# Power_toll.net
KiCad netlist of a schematic drawn in Altium Designer
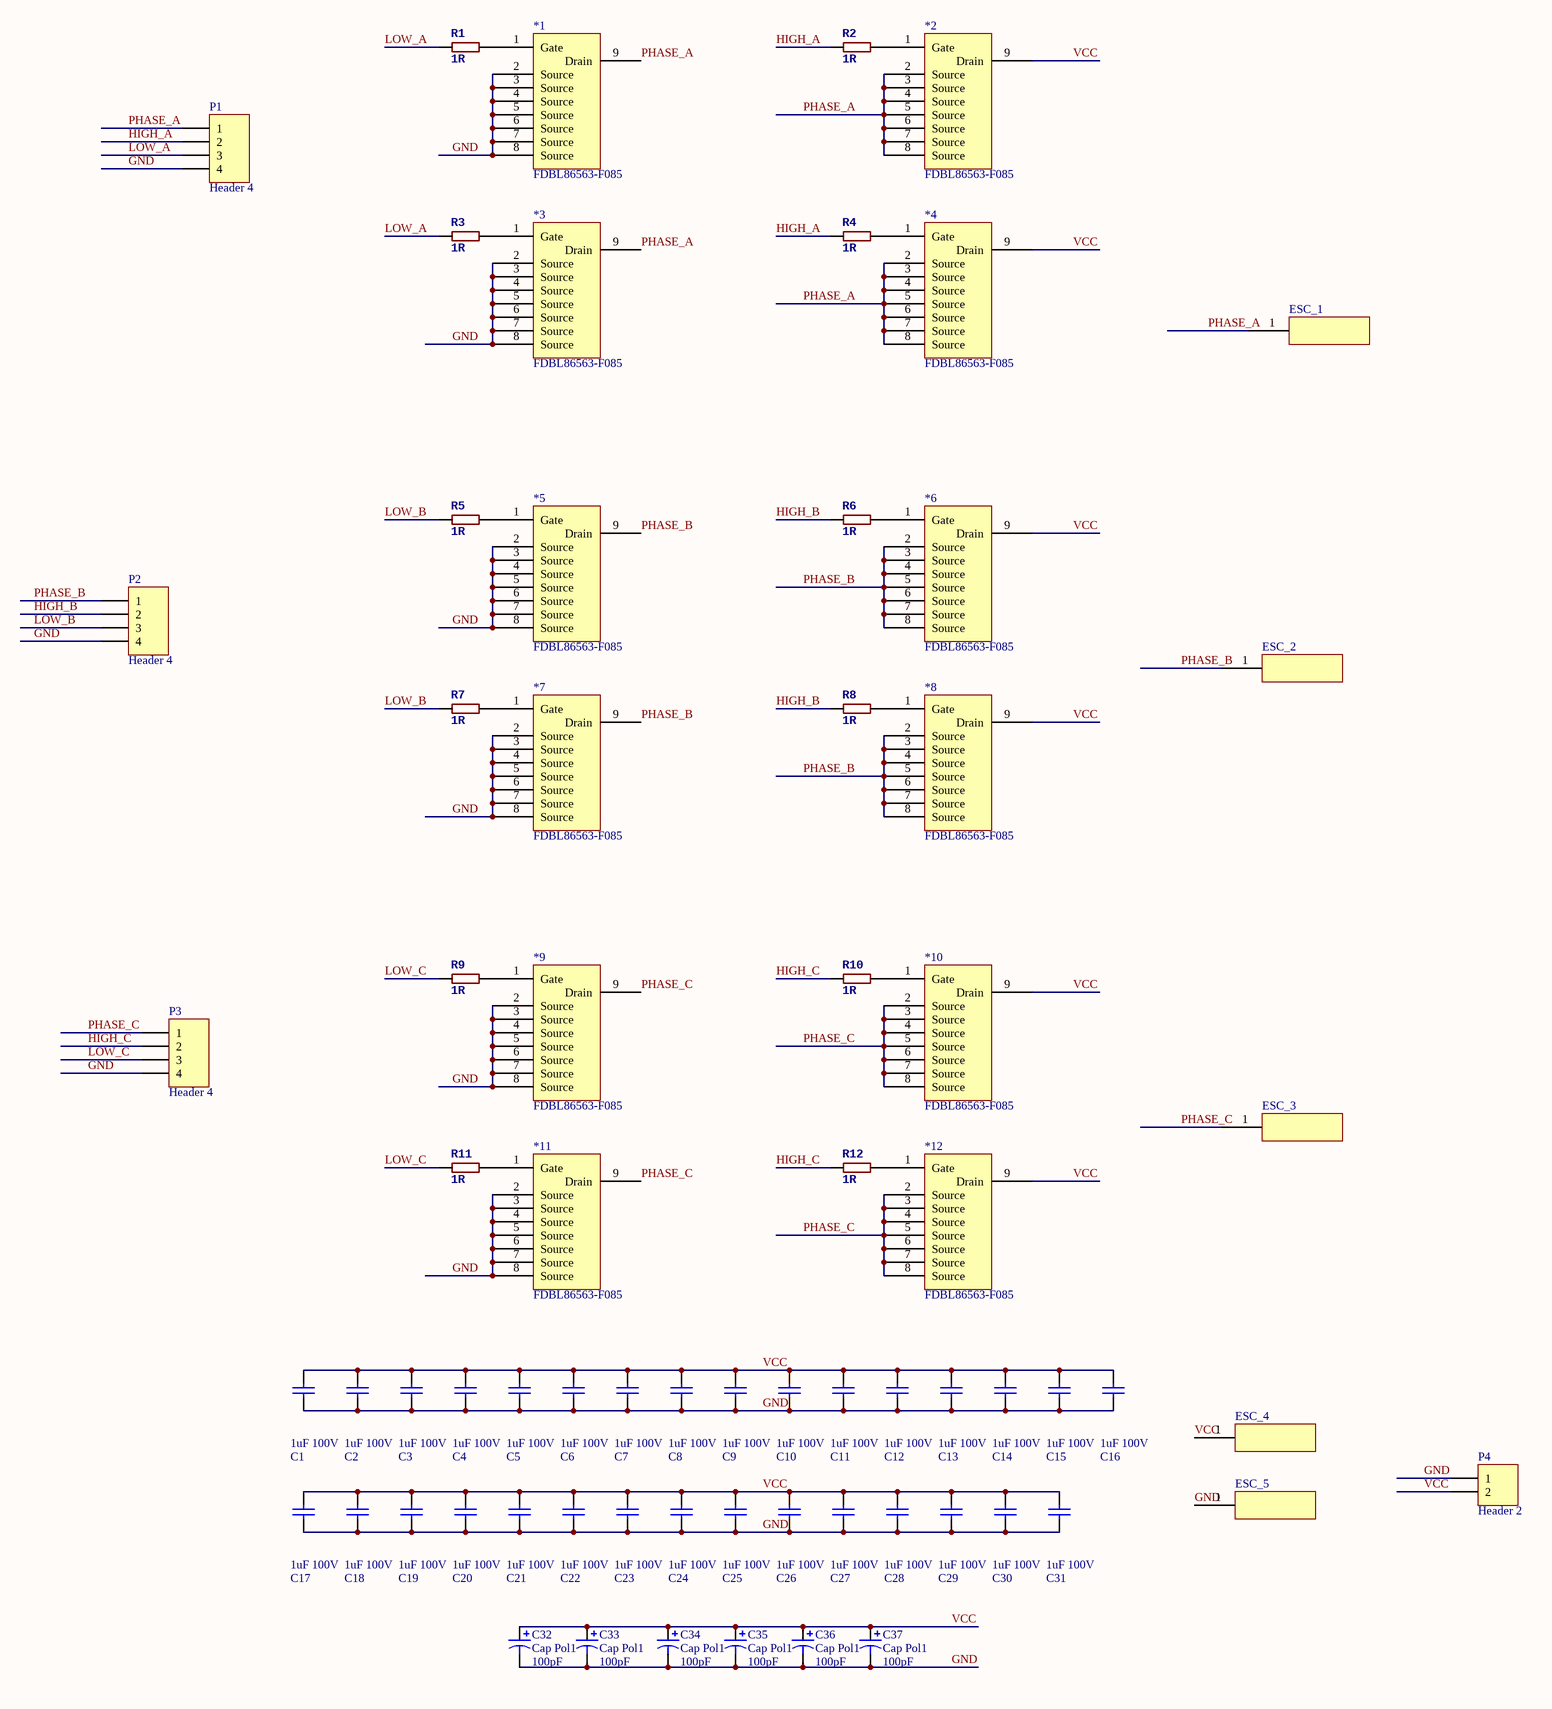
[diagram p0: Power_toll.SchDoc]

(export (version "E")
  (design (tool "Eeschema 10.0.6"))
  (components
    (comp (ref "*1")
      (value "FDBL86563-F085")
      (footprint "FDBL86563-F085")
      (libsource (lib "FDBL86563-F085") (part "FDBL86563-F085"))
    )
    (comp (ref "*2")
      (value "FDBL86563-F085")
      (footprint "FDBL86563-F085")
      (libsource (lib "FDBL86563-F085") (part "FDBL86563-F085"))
    )
    (comp (ref "*3")
      (value "FDBL86563-F085")
      (footprint "FDBL86563-F085")
      (libsource (lib "FDBL86563-F085") (part "FDBL86563-F085"))
    )
    (comp (ref "*4")
      (value "FDBL86563-F085")
      (footprint "FDBL86563-F085")
      (libsource (lib "FDBL86563-F085") (part "FDBL86563-F085"))
    )
    (comp (ref "*5")
      (value "FDBL86563-F085")
      (footprint "FDBL86563-F085")
      (libsource (lib "FDBL86563-F085") (part "FDBL86563-F085"))
    )
    (comp (ref "*6")
      (value "FDBL86563-F085")
      (footprint "FDBL86563-F085")
      (libsource (lib "FDBL86563-F085") (part "FDBL86563-F085"))
    )
    (comp (ref "*7")
      (value "FDBL86563-F085")
      (footprint "FDBL86563-F085")
      (libsource (lib "FDBL86563-F085") (part "FDBL86563-F085"))
    )
    (comp (ref "*8")
      (value "FDBL86563-F085")
      (footprint "FDBL86563-F085")
      (libsource (lib "FDBL86563-F085") (part "FDBL86563-F085"))
    )
    (comp (ref "*9")
      (value "FDBL86563-F085")
      (footprint "FDBL86563-F085")
      (libsource (lib "FDBL86563-F085") (part "FDBL86563-F085"))
    )
    (comp (ref "*10")
      (value "FDBL86563-F085")
      (footprint "FDBL86563-F085")
      (libsource (lib "FDBL86563-F085") (part "FDBL86563-F085"))
    )
    (comp (ref "*11")
      (value "FDBL86563-F085")
      (footprint "FDBL86563-F085")
      (libsource (lib "FDBL86563-F085") (part "FDBL86563-F085"))
    )
    (comp (ref "*12")
      (value "FDBL86563-F085")
      (footprint "FDBL86563-F085")
      (libsource (lib "FDBL86563-F085") (part "FDBL86563-F085"))
    )
    (comp (ref "C1")
      (value "1uF 100V")
      (footprint "C1206")
      (description "Capacitor (Semiconductor SIM Model)")
      (fields (field (name "PUBLISHER") "Altium Limited"))
      (libsource (lib "Miscellaneous Devices") (part "Cap Semi"))
    )
    (comp (ref "C2")
      (value "1uF 100V")
      (footprint "C1206")
      (description "Capacitor (Semiconductor SIM Model)")
      (fields (field (name "PUBLISHER") "Altium Limited"))
      (libsource (lib "Miscellaneous Devices") (part "Cap Semi"))
    )
    (comp (ref "C3")
      (value "1uF 100V")
      (footprint "C1206")
      (description "Capacitor (Semiconductor SIM Model)")
      (fields (field (name "PUBLISHER") "Altium Limited"))
      (libsource (lib "Miscellaneous Devices") (part "Cap Semi"))
    )
    (comp (ref "C4")
      (value "1uF 100V")
      (footprint "C1206")
      (description "Capacitor (Semiconductor SIM Model)")
      (fields (field (name "PUBLISHER") "Altium Limited"))
      (libsource (lib "Miscellaneous Devices") (part "Cap Semi"))
    )
    (comp (ref "C5")
      (value "1uF 100V")
      (footprint "C1206")
      (description "Capacitor (Semiconductor SIM Model)")
      (fields (field (name "PUBLISHER") "Altium Limited"))
      (libsource (lib "Miscellaneous Devices") (part "Cap Semi"))
    )
    (comp (ref "C6")
      (value "1uF 100V")
      (footprint "C1206")
      (description "Capacitor (Semiconductor SIM Model)")
      (fields (field (name "PUBLISHER") "Altium Limited"))
      (libsource (lib "Miscellaneous Devices") (part "Cap Semi"))
    )
    (comp (ref "C7")
      (value "1uF 100V")
      (footprint "C1206")
      (description "Capacitor (Semiconductor SIM Model)")
      (fields (field (name "PUBLISHER") "Altium Limited"))
      (libsource (lib "Miscellaneous Devices") (part "Cap Semi"))
    )
    (comp (ref "C8")
      (value "1uF 100V")
      (footprint "C1206")
      (description "Capacitor (Semiconductor SIM Model)")
      (fields (field (name "PUBLISHER") "Altium Limited"))
      (libsource (lib "Miscellaneous Devices") (part "Cap Semi"))
    )
    (comp (ref "C9")
      (value "1uF 100V")
      (footprint "C1206")
      (description "Capacitor (Semiconductor SIM Model)")
      (fields (field (name "PUBLISHER") "Altium Limited"))
      (libsource (lib "Miscellaneous Devices") (part "Cap Semi"))
    )
    (comp (ref "C10")
      (value "1uF 100V")
      (footprint "C1206")
      (description "Capacitor (Semiconductor SIM Model)")
      (fields (field (name "PUBLISHER") "Altium Limited"))
      (libsource (lib "Miscellaneous Devices") (part "Cap Semi"))
    )
    (comp (ref "C11")
      (value "1uF 100V")
      (footprint "C1206")
      (description "Capacitor (Semiconductor SIM Model)")
      (fields (field (name "PUBLISHER") "Altium Limited"))
      (libsource (lib "Miscellaneous Devices") (part "Cap Semi"))
    )
    (comp (ref "C12")
      (value "1uF 100V")
      (footprint "C1206")
      (description "Capacitor (Semiconductor SIM Model)")
      (fields (field (name "PUBLISHER") "Altium Limited"))
      (libsource (lib "Miscellaneous Devices") (part "Cap Semi"))
    )
    (comp (ref "C13")
      (value "1uF 100V")
      (footprint "C1206")
      (description "Capacitor (Semiconductor SIM Model)")
      (fields (field (name "PUBLISHER") "Altium Limited"))
      (libsource (lib "Miscellaneous Devices") (part "Cap Semi"))
    )
    (comp (ref "C14")
      (value "1uF 100V")
      (footprint "C1206")
      (description "Capacitor (Semiconductor SIM Model)")
      (fields (field (name "PUBLISHER") "Altium Limited"))
      (libsource (lib "Miscellaneous Devices") (part "Cap Semi"))
    )
    (comp (ref "C15")
      (value "1uF 100V")
      (footprint "C1206")
      (description "Capacitor (Semiconductor SIM Model)")
      (fields (field (name "PUBLISHER") "Altium Limited"))
      (libsource (lib "Miscellaneous Devices") (part "Cap Semi"))
    )
    (comp (ref "C16")
      (value "1uF 100V")
      (footprint "C1206")
      (description "Capacitor (Semiconductor SIM Model)")
      (fields (field (name "PUBLISHER") "Altium Limited"))
      (libsource (lib "Miscellaneous Devices") (part "Cap Semi"))
    )
    (comp (ref "C17")
      (value "1uF 100V")
      (footprint "C1206")
      (description "Capacitor (Semiconductor SIM Model)")
      (fields (field (name "PUBLISHER") "Altium Limited"))
      (libsource (lib "Miscellaneous Devices") (part "Cap Semi"))
    )
    (comp (ref "C18")
      (value "1uF 100V")
      (footprint "C1206")
      (description "Capacitor (Semiconductor SIM Model)")
      (fields (field (name "PUBLISHER") "Altium Limited"))
      (libsource (lib "Miscellaneous Devices") (part "Cap Semi"))
    )
    (comp (ref "C19")
      (value "1uF 100V")
      (footprint "C1206")
      (description "Capacitor (Semiconductor SIM Model)")
      (fields (field (name "PUBLISHER") "Altium Limited"))
      (libsource (lib "Miscellaneous Devices") (part "Cap Semi"))
    )
    (comp (ref "C20")
      (value "1uF 100V")
      (footprint "C1206")
      (description "Capacitor (Semiconductor SIM Model)")
      (fields (field (name "PUBLISHER") "Altium Limited"))
      (libsource (lib "Miscellaneous Devices") (part "Cap Semi"))
    )
    (comp (ref "C21")
      (value "1uF 100V")
      (footprint "C1206")
      (description "Capacitor (Semiconductor SIM Model)")
      (fields (field (name "PUBLISHER") "Altium Limited"))
      (libsource (lib "Miscellaneous Devices") (part "Cap Semi"))
    )
    (comp (ref "C22")
      (value "1uF 100V")
      (footprint "C1206")
      (description "Capacitor (Semiconductor SIM Model)")
      (fields (field (name "PUBLISHER") "Altium Limited"))
      (libsource (lib "Miscellaneous Devices") (part "Cap Semi"))
    )
    (comp (ref "C23")
      (value "1uF 100V")
      (footprint "C1206")
      (description "Capacitor (Semiconductor SIM Model)")
      (fields (field (name "PUBLISHER") "Altium Limited"))
      (libsource (lib "Miscellaneous Devices") (part "Cap Semi"))
    )
    (comp (ref "C24")
      (value "1uF 100V")
      (footprint "C1206")
      (description "Capacitor (Semiconductor SIM Model)")
      (fields (field (name "PUBLISHER") "Altium Limited"))
      (libsource (lib "Miscellaneous Devices") (part "Cap Semi"))
    )
    (comp (ref "C25")
      (value "1uF 100V")
      (footprint "C1206")
      (description "Capacitor (Semiconductor SIM Model)")
      (fields (field (name "PUBLISHER") "Altium Limited"))
      (libsource (lib "Miscellaneous Devices") (part "Cap Semi"))
    )
    (comp (ref "C26")
      (value "1uF 100V")
      (footprint "C1206")
      (description "Capacitor (Semiconductor SIM Model)")
      (fields (field (name "PUBLISHER") "Altium Limited"))
      (libsource (lib "Miscellaneous Devices") (part "Cap Semi"))
    )
    (comp (ref "C27")
      (value "1uF 100V")
      (footprint "C1206")
      (description "Capacitor (Semiconductor SIM Model)")
      (fields (field (name "PUBLISHER") "Altium Limited"))
      (libsource (lib "Miscellaneous Devices") (part "Cap Semi"))
    )
    (comp (ref "C28")
      (value "1uF 100V")
      (footprint "C1206")
      (description "Capacitor (Semiconductor SIM Model)")
      (fields (field (name "PUBLISHER") "Altium Limited"))
      (libsource (lib "Miscellaneous Devices") (part "Cap Semi"))
    )
    (comp (ref "C29")
      (value "1uF 100V")
      (footprint "C1206")
      (description "Capacitor (Semiconductor SIM Model)")
      (fields (field (name "PUBLISHER") "Altium Limited"))
      (libsource (lib "Miscellaneous Devices") (part "Cap Semi"))
    )
    (comp (ref "C30")
      (value "1uF 100V")
      (footprint "C1206")
      (description "Capacitor (Semiconductor SIM Model)")
      (fields (field (name "PUBLISHER") "Altium Limited"))
      (libsource (lib "Miscellaneous Devices") (part "Cap Semi"))
    )
    (comp (ref "C31")
      (value "1uF 100V")
      (footprint "C1206")
      (description "Capacitor (Semiconductor SIM Model)")
      (fields (field (name "PUBLISHER") "Altium Limited"))
      (libsource (lib "Miscellaneous Devices") (part "Cap Semi"))
    )
    (comp (ref "C32")
      (value "Cap Pol1")
      (footprint "RB5-10.5")
      (description "Polarized Capacitor (Radial)")
      (fields (field (name "ALTIUM_VALUE") "100pF") (field (name "PUBLISHER") "Altium Limited"))
      (libsource (lib "Miscellaneous Devices") (part "Cap Pol1"))
    )
    (comp (ref "C33")
      (value "Cap Pol1")
      (footprint "RB5-10.5")
      (description "Polarized Capacitor (Radial)")
      (fields (field (name "ALTIUM_VALUE") "100pF") (field (name "PUBLISHER") "Altium Limited"))
      (libsource (lib "Miscellaneous Devices") (part "Cap Pol1"))
    )
    (comp (ref "C34")
      (value "Cap Pol1")
      (footprint "RB5-10.5")
      (description "Polarized Capacitor (Radial)")
      (fields (field (name "ALTIUM_VALUE") "100pF") (field (name "PUBLISHER") "Altium Limited"))
      (libsource (lib "Miscellaneous Devices") (part "Cap Pol1"))
    )
    (comp (ref "C35")
      (value "Cap Pol1")
      (footprint "RB5-10.5")
      (description "Polarized Capacitor (Radial)")
      (fields (field (name "ALTIUM_VALUE") "100pF") (field (name "PUBLISHER") "Altium Limited"))
      (libsource (lib "Miscellaneous Devices") (part "Cap Pol1"))
    )
    (comp (ref "C36")
      (value "Cap Pol1")
      (footprint "RB5-10.5")
      (description "Polarized Capacitor (Radial)")
      (fields (field (name "ALTIUM_VALUE") "100pF") (field (name "PUBLISHER") "Altium Limited"))
      (libsource (lib "Miscellaneous Devices") (part "Cap Pol1"))
    )
    (comp (ref "C37")
      (value "Cap Pol1")
      (footprint "RB5-10.5")
      (description "Polarized Capacitor (Radial)")
      (fields (field (name "ALTIUM_VALUE") "100pF") (field (name "PUBLISHER") "Altium Limited"))
      (libsource (lib "Miscellaneous Devices") (part "Cap Pol1"))
    )
    (comp (ref "ESC_1")
      (value "Component_1")
      (footprint "power_terminal")
      (libsource (lib "power_terminal") (part "Component_1"))
    )
    (comp (ref "ESC_2")
      (value "Component_1")
      (footprint "power_terminal")
      (libsource (lib "power_terminal") (part "Component_1"))
    )
    (comp (ref "ESC_3")
      (value "Component_1")
      (footprint "power_terminal")
      (libsource (lib "power_terminal") (part "Component_1"))
    )
    (comp (ref "ESC_4")
      (value "Component_1")
      (footprint "power_terminal")
      (libsource (lib "power_terminal") (part "Component_1"))
    )
    (comp (ref "ESC_5")
      (value "Component_1")
      (footprint "power_terminal")
      (libsource (lib "power_terminal") (part "Component_1"))
    )
    (comp (ref "P1")
      (value "Header 4")
      (footprint "HDR1X4")
      (description "Header, 4-Pin")
      (fields (field (name "PUBLISHER") "Altium Limited"))
      (libsource (lib "Miscellaneous Connectors") (part "Header 4"))
    )
    (comp (ref "P2")
      (value "Header 4")
      (footprint "HDR1X4")
      (description "Header, 4-Pin")
      (fields (field (name "PUBLISHER") "Altium Limited"))
      (libsource (lib "Miscellaneous Connectors") (part "Header 4"))
    )
    (comp (ref "P3")
      (value "Header 4")
      (footprint "HDR1X4")
      (description "Header, 4-Pin")
      (fields (field (name "PUBLISHER") "Altium Limited"))
      (libsource (lib "Miscellaneous Connectors") (part "Header 4"))
    )
    (comp (ref "P4")
      (value "Header 2")
      (footprint "HDR1X2")
      (description "Header, 2-Pin")
      (fields (field (name "PUBLISHER") "Altium Limited"))
      (libsource (lib "Miscellaneous Connectors") (part "Header 2"))
    )
    (comp (ref "R1")
      (value "1R")
      (footprint "1608[0603]")
      (libsource (lib "sapog_reference_hardware") (part "R0402"))
    )
    (comp (ref "R2")
      (value "1R")
      (footprint "1608[0603]")
      (libsource (lib "sapog_reference_hardware") (part "R0402"))
    )
    (comp (ref "R3")
      (value "1R")
      (footprint "1608[0603]")
      (libsource (lib "sapog_reference_hardware") (part "R0402"))
    )
    (comp (ref "R4")
      (value "1R")
      (footprint "1608[0603]")
      (libsource (lib "sapog_reference_hardware") (part "R0402"))
    )
    (comp (ref "R5")
      (value "1R")
      (footprint "1608[0603]")
      (libsource (lib "sapog_reference_hardware") (part "R0402"))
    )
    (comp (ref "R6")
      (value "1R")
      (footprint "1608[0603]")
      (libsource (lib "sapog_reference_hardware") (part "R0402"))
    )
    (comp (ref "R7")
      (value "1R")
      (footprint "1608[0603]")
      (libsource (lib "sapog_reference_hardware") (part "R0402"))
    )
    (comp (ref "R8")
      (value "1R")
      (footprint "1608[0603]")
      (libsource (lib "sapog_reference_hardware") (part "R0402"))
    )
    (comp (ref "R9")
      (value "1R")
      (footprint "1608[0603]")
      (libsource (lib "sapog_reference_hardware") (part "R0402"))
    )
    (comp (ref "R10")
      (value "1R")
      (footprint "1608[0603]")
      (libsource (lib "sapog_reference_hardware") (part "R0402"))
    )
    (comp (ref "R11")
      (value "1R")
      (footprint "1608[0603]")
      (libsource (lib "sapog_reference_hardware") (part "R0402"))
    )
    (comp (ref "R12")
      (value "1R")
      (footprint "1608[0603]")
      (libsource (lib "sapog_reference_hardware") (part "R0402"))
    )
  )
  (nets
    (net (code "1") (name "/GND") (class "Default")
      (node (ref "*1") (pin "2") (pinfunction "Source_2") (pintype "passive"))
      (node (ref "*1") (pin "3") (pinfunction "Source_3") (pintype "passive"))
      (node (ref "*1") (pin "4") (pinfunction "Source_4") (pintype "passive"))
      (node (ref "*1") (pin "5") (pinfunction "Source_5") (pintype "passive"))
      (node (ref "*1") (pin "6") (pinfunction "Source_6") (pintype "passive"))
      (node (ref "*1") (pin "7") (pinfunction "Source_7") (pintype "passive"))
      (node (ref "*1") (pin "8") (pinfunction "Source_8") (pintype "passive"))
      (node (ref "*11") (pin "2") (pinfunction "Source_2") (pintype "passive"))
      (node (ref "*11") (pin "3") (pinfunction "Source_3") (pintype "passive"))
      (node (ref "*11") (pin "4") (pinfunction "Source_4") (pintype "passive"))
      (node (ref "*11") (pin "5") (pinfunction "Source_5") (pintype "passive"))
      (node (ref "*11") (pin "6") (pinfunction "Source_6") (pintype "passive"))
      (node (ref "*11") (pin "7") (pinfunction "Source_7") (pintype "passive"))
      (node (ref "*11") (pin "8") (pinfunction "Source_8") (pintype "passive"))
      (node (ref "*3") (pin "2") (pinfunction "Source_2") (pintype "passive"))
      (node (ref "*3") (pin "3") (pinfunction "Source_3") (pintype "passive"))
      (node (ref "*3") (pin "4") (pinfunction "Source_4") (pintype "passive"))
      (node (ref "*3") (pin "5") (pinfunction "Source_5") (pintype "passive"))
      (node (ref "*3") (pin "6") (pinfunction "Source_6") (pintype "passive"))
      (node (ref "*3") (pin "7") (pinfunction "Source_7") (pintype "passive"))
      (node (ref "*3") (pin "8") (pinfunction "Source_8") (pintype "passive"))
      (node (ref "*5") (pin "2") (pinfunction "Source_2") (pintype "passive"))
      (node (ref "*5") (pin "3") (pinfunction "Source_3") (pintype "passive"))
      (node (ref "*5") (pin "4") (pinfunction "Source_4") (pintype "passive"))
      (node (ref "*5") (pin "5") (pinfunction "Source_5") (pintype "passive"))
      (node (ref "*5") (pin "6") (pinfunction "Source_6") (pintype "passive"))
      (node (ref "*5") (pin "7") (pinfunction "Source_7") (pintype "passive"))
      (node (ref "*5") (pin "8") (pinfunction "Source_8") (pintype "passive"))
      (node (ref "*7") (pin "2") (pinfunction "Source_2") (pintype "passive"))
      (node (ref "*7") (pin "3") (pinfunction "Source_3") (pintype "passive"))
      (node (ref "*7") (pin "4") (pinfunction "Source_4") (pintype "passive"))
      (node (ref "*7") (pin "5") (pinfunction "Source_5") (pintype "passive"))
      (node (ref "*7") (pin "6") (pinfunction "Source_6") (pintype "passive"))
      (node (ref "*7") (pin "7") (pinfunction "Source_7") (pintype "passive"))
      (node (ref "*7") (pin "8") (pinfunction "Source_8") (pintype "passive"))
      (node (ref "*9") (pin "2") (pinfunction "Source_2") (pintype "passive"))
      (node (ref "*9") (pin "3") (pinfunction "Source_3") (pintype "passive"))
      (node (ref "*9") (pin "4") (pinfunction "Source_4") (pintype "passive"))
      (node (ref "*9") (pin "5") (pinfunction "Source_5") (pintype "passive"))
      (node (ref "*9") (pin "6") (pinfunction "Source_6") (pintype "passive"))
      (node (ref "*9") (pin "7") (pinfunction "Source_7") (pintype "passive"))
      (node (ref "*9") (pin "8") (pinfunction "Source_8") (pintype "passive"))
      (node (ref "C1") (pin "1") (pinfunction "1_1") (pintype "passive"))
      (node (ref "C10") (pin "1") (pinfunction "1_1") (pintype "passive"))
      (node (ref "C11") (pin "1") (pinfunction "1_1") (pintype "passive"))
      (node (ref "C12") (pin "1") (pinfunction "1_1") (pintype "passive"))
      (node (ref "C13") (pin "1") (pinfunction "1_1") (pintype "passive"))
      (node (ref "C14") (pin "1") (pinfunction "1_1") (pintype "passive"))
      (node (ref "C15") (pin "1") (pinfunction "1_1") (pintype "passive"))
      (node (ref "C16") (pin "1") (pinfunction "1_1") (pintype "passive"))
      (node (ref "C17") (pin "1") (pinfunction "1_1") (pintype "passive"))
      (node (ref "C18") (pin "1") (pinfunction "1_1") (pintype "passive"))
      (node (ref "C19") (pin "1") (pinfunction "1_1") (pintype "passive"))
      (node (ref "C2") (pin "1") (pinfunction "1_1") (pintype "passive"))
      (node (ref "C20") (pin "1") (pinfunction "1_1") (pintype "passive"))
      (node (ref "C21") (pin "1") (pinfunction "1_1") (pintype "passive"))
      (node (ref "C22") (pin "1") (pinfunction "1_1") (pintype "passive"))
      (node (ref "C23") (pin "1") (pinfunction "1_1") (pintype "passive"))
      (node (ref "C24") (pin "1") (pinfunction "1_1") (pintype "passive"))
      (node (ref "C25") (pin "1") (pinfunction "1_1") (pintype "passive"))
      (node (ref "C26") (pin "1") (pinfunction "1_1") (pintype "passive"))
      (node (ref "C27") (pin "1") (pinfunction "1_1") (pintype "passive"))
      (node (ref "C28") (pin "1") (pinfunction "1_1") (pintype "passive"))
      (node (ref "C29") (pin "1") (pinfunction "1_1") (pintype "passive"))
      (node (ref "C3") (pin "1") (pinfunction "1_1") (pintype "passive"))
      (node (ref "C30") (pin "1") (pinfunction "1_1") (pintype "passive"))
      (node (ref "C31") (pin "1") (pinfunction "1_1") (pintype "passive"))
      (node (ref "C32") (pin "2") (pinfunction "2_2") (pintype "passive"))
      (node (ref "C33") (pin "2") (pinfunction "2_2") (pintype "passive"))
      (node (ref "C34") (pin "2") (pinfunction "2_2") (pintype "passive"))
      (node (ref "C35") (pin "2") (pinfunction "2_2") (pintype "passive"))
      (node (ref "C36") (pin "2") (pinfunction "2_2") (pintype "passive"))
      (node (ref "C37") (pin "2") (pinfunction "2_2") (pintype "passive"))
      (node (ref "C4") (pin "1") (pinfunction "1_1") (pintype "passive"))
      (node (ref "C5") (pin "1") (pinfunction "1_1") (pintype "passive"))
      (node (ref "C6") (pin "1") (pinfunction "1_1") (pintype "passive"))
      (node (ref "C7") (pin "1") (pinfunction "1_1") (pintype "passive"))
      (node (ref "C8") (pin "1") (pinfunction "1_1") (pintype "passive"))
      (node (ref "C9") (pin "1") (pinfunction "1_1") (pintype "passive"))
      (node (ref "ESC_5") (pin "1") (pintype "passive"))
      (node (ref "P1") (pin "4") (pinfunction "4_4") (pintype "passive"))
      (node (ref "P2") (pin "4") (pinfunction "4_4") (pintype "passive"))
      (node (ref "P3") (pin "4") (pinfunction "4_4") (pintype "passive"))
      (node (ref "P4") (pin "1") (pinfunction "1_1") (pintype "passive"))
    )
    (net (code "2") (name "/HIGH_A") (class "Default")
      (node (ref "P1") (pin "2") (pinfunction "2_2") (pintype "passive"))
      (node (ref "R2") (pin "2") (pinfunction "2_2") (pintype "passive"))
      (node (ref "R4") (pin "2") (pinfunction "2_2") (pintype "passive"))
    )
    (net (code "3") (name "/HIGH_B") (class "Default")
      (node (ref "P2") (pin "2") (pinfunction "2_2") (pintype "passive"))
      (node (ref "R6") (pin "2") (pinfunction "2_2") (pintype "passive"))
      (node (ref "R8") (pin "2") (pinfunction "2_2") (pintype "passive"))
    )
    (net (code "4") (name "/HIGH_C") (class "Default")
      (node (ref "P3") (pin "2") (pinfunction "2_2") (pintype "passive"))
      (node (ref "R10") (pin "2") (pinfunction "2_2") (pintype "passive"))
      (node (ref "R12") (pin "2") (pinfunction "2_2") (pintype "passive"))
    )
    (net (code "5") (name "/LOW_A") (class "Default")
      (node (ref "P1") (pin "3") (pinfunction "3_3") (pintype "passive"))
      (node (ref "R1") (pin "2") (pinfunction "2_2") (pintype "passive"))
      (node (ref "R3") (pin "2") (pinfunction "2_2") (pintype "passive"))
    )
    (net (code "6") (name "/LOW_B") (class "Default")
      (node (ref "P2") (pin "3") (pinfunction "3_3") (pintype "passive"))
      (node (ref "R5") (pin "2") (pinfunction "2_2") (pintype "passive"))
      (node (ref "R7") (pin "2") (pinfunction "2_2") (pintype "passive"))
    )
    (net (code "7") (name "/LOW_C") (class "Default")
      (node (ref "P3") (pin "3") (pinfunction "3_3") (pintype "passive"))
      (node (ref "R11") (pin "2") (pinfunction "2_2") (pintype "passive"))
      (node (ref "R9") (pin "2") (pinfunction "2_2") (pintype "passive"))
    )
    (net (code "8") (name "/PHASE_A") (class "Default")
      (node (ref "*1") (pin "9") (pinfunction "Drain_9") (pintype "passive"))
      (node (ref "*2") (pin "2") (pinfunction "Source_2") (pintype "passive"))
      (node (ref "*2") (pin "3") (pinfunction "Source_3") (pintype "passive"))
      (node (ref "*2") (pin "4") (pinfunction "Source_4") (pintype "passive"))
      (node (ref "*2") (pin "5") (pinfunction "Source_5") (pintype "passive"))
      (node (ref "*2") (pin "6") (pinfunction "Source_6") (pintype "passive"))
      (node (ref "*2") (pin "7") (pinfunction "Source_7") (pintype "passive"))
      (node (ref "*2") (pin "8") (pinfunction "Source_8") (pintype "passive"))
      (node (ref "*3") (pin "9") (pinfunction "Drain_9") (pintype "passive"))
      (node (ref "*4") (pin "2") (pinfunction "Source_2") (pintype "passive"))
      (node (ref "*4") (pin "3") (pinfunction "Source_3") (pintype "passive"))
      (node (ref "*4") (pin "4") (pinfunction "Source_4") (pintype "passive"))
      (node (ref "*4") (pin "5") (pinfunction "Source_5") (pintype "passive"))
      (node (ref "*4") (pin "6") (pinfunction "Source_6") (pintype "passive"))
      (node (ref "*4") (pin "7") (pinfunction "Source_7") (pintype "passive"))
      (node (ref "*4") (pin "8") (pinfunction "Source_8") (pintype "passive"))
      (node (ref "ESC_1") (pin "1") (pintype "passive"))
      (node (ref "P1") (pin "1") (pinfunction "1_1") (pintype "passive"))
    )
    (net (code "9") (name "/PHASE_B") (class "Default")
      (node (ref "*5") (pin "9") (pinfunction "Drain_9") (pintype "passive"))
      (node (ref "*6") (pin "2") (pinfunction "Source_2") (pintype "passive"))
      (node (ref "*6") (pin "3") (pinfunction "Source_3") (pintype "passive"))
      (node (ref "*6") (pin "4") (pinfunction "Source_4") (pintype "passive"))
      (node (ref "*6") (pin "5") (pinfunction "Source_5") (pintype "passive"))
      (node (ref "*6") (pin "6") (pinfunction "Source_6") (pintype "passive"))
      (node (ref "*6") (pin "7") (pinfunction "Source_7") (pintype "passive"))
      (node (ref "*6") (pin "8") (pinfunction "Source_8") (pintype "passive"))
      (node (ref "*7") (pin "9") (pinfunction "Drain_9") (pintype "passive"))
      (node (ref "*8") (pin "2") (pinfunction "Source_2") (pintype "passive"))
      (node (ref "*8") (pin "3") (pinfunction "Source_3") (pintype "passive"))
      (node (ref "*8") (pin "4") (pinfunction "Source_4") (pintype "passive"))
      (node (ref "*8") (pin "5") (pinfunction "Source_5") (pintype "passive"))
      (node (ref "*8") (pin "6") (pinfunction "Source_6") (pintype "passive"))
      (node (ref "*8") (pin "7") (pinfunction "Source_7") (pintype "passive"))
      (node (ref "*8") (pin "8") (pinfunction "Source_8") (pintype "passive"))
      (node (ref "ESC_2") (pin "1") (pintype "passive"))
      (node (ref "P2") (pin "1") (pinfunction "1_1") (pintype "passive"))
    )
    (net (code "10") (name "/PHASE_C") (class "Default")
      (node (ref "*10") (pin "2") (pinfunction "Source_2") (pintype "passive"))
      (node (ref "*10") (pin "3") (pinfunction "Source_3") (pintype "passive"))
      (node (ref "*10") (pin "4") (pinfunction "Source_4") (pintype "passive"))
      (node (ref "*10") (pin "5") (pinfunction "Source_5") (pintype "passive"))
      (node (ref "*10") (pin "6") (pinfunction "Source_6") (pintype "passive"))
      (node (ref "*10") (pin "7") (pinfunction "Source_7") (pintype "passive"))
      (node (ref "*10") (pin "8") (pinfunction "Source_8") (pintype "passive"))
      (node (ref "*11") (pin "9") (pinfunction "Drain_9") (pintype "passive"))
      (node (ref "*12") (pin "2") (pinfunction "Source_2") (pintype "passive"))
      (node (ref "*12") (pin "3") (pinfunction "Source_3") (pintype "passive"))
      (node (ref "*12") (pin "4") (pinfunction "Source_4") (pintype "passive"))
      (node (ref "*12") (pin "5") (pinfunction "Source_5") (pintype "passive"))
      (node (ref "*12") (pin "6") (pinfunction "Source_6") (pintype "passive"))
      (node (ref "*12") (pin "7") (pinfunction "Source_7") (pintype "passive"))
      (node (ref "*12") (pin "8") (pinfunction "Source_8") (pintype "passive"))
      (node (ref "*9") (pin "9") (pinfunction "Drain_9") (pintype "passive"))
      (node (ref "ESC_3") (pin "1") (pintype "passive"))
      (node (ref "P3") (pin "1") (pinfunction "1_1") (pintype "passive"))
    )
    (net (code "11") (name "/VCC") (class "Default")
      (node (ref "*10") (pin "9") (pinfunction "Drain_9") (pintype "passive"))
      (node (ref "*12") (pin "9") (pinfunction "Drain_9") (pintype "passive"))
      (node (ref "*2") (pin "9") (pinfunction "Drain_9") (pintype "passive"))
      (node (ref "*4") (pin "9") (pinfunction "Drain_9") (pintype "passive"))
      (node (ref "*6") (pin "9") (pinfunction "Drain_9") (pintype "passive"))
      (node (ref "*8") (pin "9") (pinfunction "Drain_9") (pintype "passive"))
      (node (ref "C1") (pin "2") (pinfunction "2_2") (pintype "passive"))
      (node (ref "C10") (pin "2") (pinfunction "2_2") (pintype "passive"))
      (node (ref "C11") (pin "2") (pinfunction "2_2") (pintype "passive"))
      (node (ref "C12") (pin "2") (pinfunction "2_2") (pintype "passive"))
      (node (ref "C13") (pin "2") (pinfunction "2_2") (pintype "passive"))
      (node (ref "C14") (pin "2") (pinfunction "2_2") (pintype "passive"))
      (node (ref "C15") (pin "2") (pinfunction "2_2") (pintype "passive"))
      (node (ref "C16") (pin "2") (pinfunction "2_2") (pintype "passive"))
      (node (ref "C17") (pin "2") (pinfunction "2_2") (pintype "passive"))
      (node (ref "C18") (pin "2") (pinfunction "2_2") (pintype "passive"))
      (node (ref "C19") (pin "2") (pinfunction "2_2") (pintype "passive"))
      (node (ref "C2") (pin "2") (pinfunction "2_2") (pintype "passive"))
      (node (ref "C20") (pin "2") (pinfunction "2_2") (pintype "passive"))
      (node (ref "C21") (pin "2") (pinfunction "2_2") (pintype "passive"))
      (node (ref "C22") (pin "2") (pinfunction "2_2") (pintype "passive"))
      (node (ref "C23") (pin "2") (pinfunction "2_2") (pintype "passive"))
      (node (ref "C24") (pin "2") (pinfunction "2_2") (pintype "passive"))
      (node (ref "C25") (pin "2") (pinfunction "2_2") (pintype "passive"))
      (node (ref "C26") (pin "2") (pinfunction "2_2") (pintype "passive"))
      (node (ref "C27") (pin "2") (pinfunction "2_2") (pintype "passive"))
      (node (ref "C28") (pin "2") (pinfunction "2_2") (pintype "passive"))
      (node (ref "C29") (pin "2") (pinfunction "2_2") (pintype "passive"))
      (node (ref "C3") (pin "2") (pinfunction "2_2") (pintype "passive"))
      (node (ref "C30") (pin "2") (pinfunction "2_2") (pintype "passive"))
      (node (ref "C31") (pin "2") (pinfunction "2_2") (pintype "passive"))
      (node (ref "C32") (pin "1") (pinfunction "1_1") (pintype "passive"))
      (node (ref "C33") (pin "1") (pinfunction "1_1") (pintype "passive"))
      (node (ref "C34") (pin "1") (pinfunction "1_1") (pintype "passive"))
      (node (ref "C35") (pin "1") (pinfunction "1_1") (pintype "passive"))
      (node (ref "C36") (pin "1") (pinfunction "1_1") (pintype "passive"))
      (node (ref "C37") (pin "1") (pinfunction "1_1") (pintype "passive"))
      (node (ref "C4") (pin "2") (pinfunction "2_2") (pintype "passive"))
      (node (ref "C5") (pin "2") (pinfunction "2_2") (pintype "passive"))
      (node (ref "C6") (pin "2") (pinfunction "2_2") (pintype "passive"))
      (node (ref "C7") (pin "2") (pinfunction "2_2") (pintype "passive"))
      (node (ref "C8") (pin "2") (pinfunction "2_2") (pintype "passive"))
      (node (ref "C9") (pin "2") (pinfunction "2_2") (pintype "passive"))
      (node (ref "ESC_4") (pin "1") (pintype "passive"))
      (node (ref "P4") (pin "2") (pinfunction "2_2") (pintype "passive"))
    )
    (net (code "12") (name "Net-(*1-Gate)") (class "Default")
      (node (ref "*1") (pin "1") (pinfunction "Gate_1") (pintype "passive"))
      (node (ref "R1") (pin "1") (pinfunction "1_1") (pintype "passive"))
    )
    (net (code "13") (name "Net-(*2-Gate)") (class "Default")
      (node (ref "*2") (pin "1") (pinfunction "Gate_1") (pintype "passive"))
      (node (ref "R2") (pin "1") (pinfunction "1_1") (pintype "passive"))
    )
    (net (code "14") (name "Net-(*3-Gate)") (class "Default")
      (node (ref "*3") (pin "1") (pinfunction "Gate_1") (pintype "passive"))
      (node (ref "R3") (pin "1") (pinfunction "1_1") (pintype "passive"))
    )
    (net (code "15") (name "Net-(*4-Gate)") (class "Default")
      (node (ref "*4") (pin "1") (pinfunction "Gate_1") (pintype "passive"))
      (node (ref "R4") (pin "1") (pinfunction "1_1") (pintype "passive"))
    )
    (net (code "16") (name "Net-(*5-Gate)") (class "Default")
      (node (ref "*5") (pin "1") (pinfunction "Gate_1") (pintype "passive"))
      (node (ref "R5") (pin "1") (pinfunction "1_1") (pintype "passive"))
    )
    (net (code "17") (name "Net-(*6-Gate)") (class "Default")
      (node (ref "*6") (pin "1") (pinfunction "Gate_1") (pintype "passive"))
      (node (ref "R6") (pin "1") (pinfunction "1_1") (pintype "passive"))
    )
    (net (code "18") (name "Net-(*7-Gate)") (class "Default")
      (node (ref "*7") (pin "1") (pinfunction "Gate_1") (pintype "passive"))
      (node (ref "R7") (pin "1") (pinfunction "1_1") (pintype "passive"))
    )
    (net (code "19") (name "Net-(*8-Gate)") (class "Default")
      (node (ref "*8") (pin "1") (pinfunction "Gate_1") (pintype "passive"))
      (node (ref "R8") (pin "1") (pinfunction "1_1") (pintype "passive"))
    )
    (net (code "20") (name "Net-(*9-Gate)") (class "Default")
      (node (ref "*9") (pin "1") (pinfunction "Gate_1") (pintype "passive"))
      (node (ref "R9") (pin "1") (pinfunction "1_1") (pintype "passive"))
    )
    (net (code "21") (name "Net-(*10-Gate)") (class "Default")
      (node (ref "*10") (pin "1") (pinfunction "Gate_1") (pintype "passive"))
      (node (ref "R10") (pin "1") (pinfunction "1_1") (pintype "passive"))
    )
    (net (code "22") (name "Net-(*11-Gate)") (class "Default")
      (node (ref "*11") (pin "1") (pinfunction "Gate_1") (pintype "passive"))
      (node (ref "R11") (pin "1") (pinfunction "1_1") (pintype "passive"))
    )
    (net (code "23") (name "Net-(*12-Gate)") (class "Default")
      (node (ref "*12") (pin "1") (pinfunction "Gate_1") (pintype "passive"))
      (node (ref "R12") (pin "1") (pinfunction "1_1") (pintype "passive"))
    )
  )
)
